# FLY_DIVER.net
KiCad netlist of a schematic drawn in Altium Designer
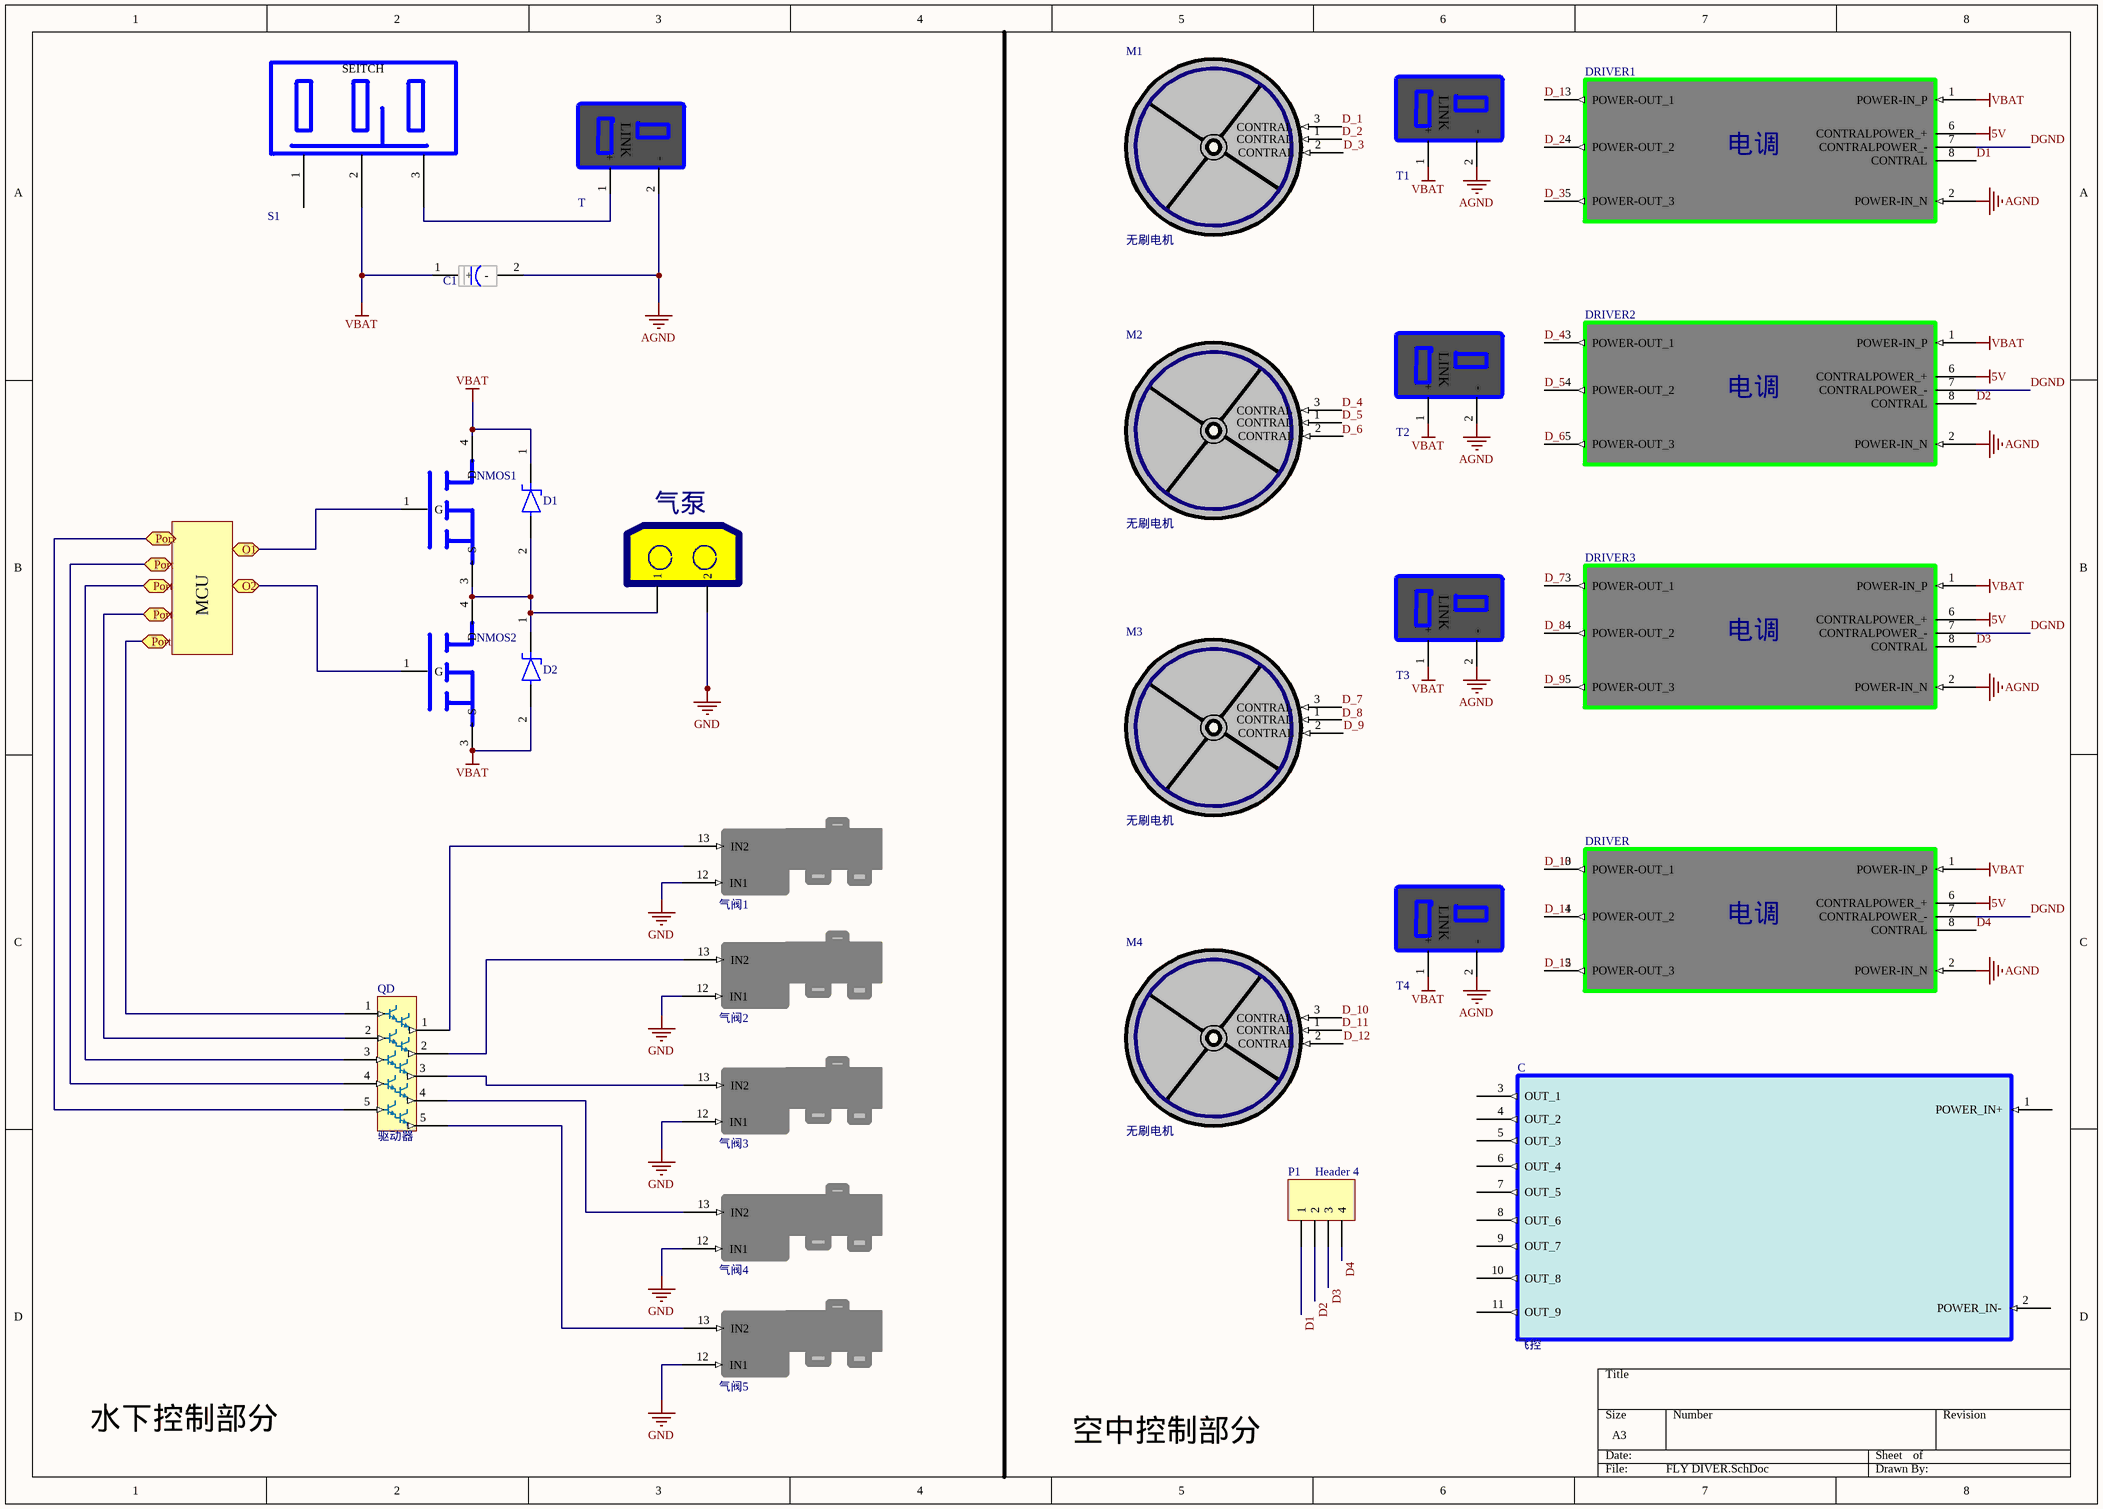
[diagram p0: FLY DIVER.SchDoc]

(export (version "E")
  (design (tool "Eeschema 10.0.6"))
  (components
    (comp (ref "*") (value "MCU") (libsource (lib "FLY DIVER") (part "MCU")))
    (comp (ref "C") (value "飞控") (libsource (lib "FLY DIVER") (part "飞控")))
    (comp (ref "C1") (value "钽电容") (footprint "钽B") (libsource (lib "常用原件库") (part "钽电容")))
    (comp (ref "D1") (value "贴片二极管") (footprint "二极管SMA") (libsource (lib "常用原件库") (part "贴片二极管")))
    (comp (ref "D2") (value "贴片二极管") (footprint "二极管SMA") (libsource (lib "常用原件库") (part "贴片二极管")))
    (comp (ref "DRIVER") (value "U?") (libsource (lib "FLY DIVER") (part "电调")))
    (comp (ref "DRIVER1") (value "U?") (libsource (lib "FLY DIVER") (part "电调")))
    (comp (ref "DRIVER2") (value "U?") (libsource (lib "FLY DIVER") (part "电调")))
    (comp (ref "DRIVER3") (value "U?") (libsource (lib "FLY DIVER") (part "电调")))
    (comp (ref "M1") (value "无刷电机") (libsource (lib "FLY DIVER") (part "无刷电机")))
    (comp (ref "M2") (value "无刷电机") (libsource (lib "FLY DIVER") (part "无刷电机")))
    (comp (ref "M3") (value "无刷电机") (libsource (lib "FLY DIVER") (part "无刷电机")))
    (comp (ref "M4") (value "无刷电机") (libsource (lib "FLY DIVER") (part "无刷电机")))
    (comp (ref "NMOS1") (value "NMOS") (footprint "NMOS") (libsource (lib "常用原件库") (part "NMOS")))
    (comp (ref "NMOS2") (value "NMOS") (footprint "NMOS") (libsource (lib "常用原件库") (part "NMOS")))
    (comp (ref "P1")
      (value "Header 4")
      (footprint "HDR1X4")
      (description "Header, 4-Pin")
      (fields (field (name "PUBLISHER") "Altium Limited"))
      (libsource (lib "Miscellaneous Connectors") (part "Header 4"))
    )
    (comp (ref "Q1") (value "气阀1") (libsource (lib "FLY DIVER") (part "气阀")))
    (comp (ref "Q2") (value "气阀2") (libsource (lib "FLY DIVER") (part "气阀")))
    (comp (ref "Q3") (value "气阀3") (libsource (lib "FLY DIVER") (part "气阀")))
    (comp (ref "Q4") (value "气阀4") (libsource (lib "FLY DIVER") (part "气阀")))
    (comp (ref "Q5") (value "气阀5") (libsource (lib "FLY DIVER") (part "气阀")))
    (comp (ref "QD") (value "驱动器") (libsource (lib "FLY DIVER") (part "驱动器")))
    (comp (ref "S1") (value "拨动开关") (footprint "拨动开关") (libsource (lib "常用原件库") (part "拨动开关")))
    (comp (ref "T") (value "T型头") (footprint "T型头") (libsource (lib "常用原件库") (part "T型头")))
    (comp (ref "T1") (value "T型头") (footprint "T型头") (libsource (lib "常用原件库") (part "T型头")))
    (comp (ref "T2") (value "T型头") (footprint "T型头") (libsource (lib "常用原件库") (part "T型头")))
    (comp (ref "T3") (value "T型头") (footprint "T型头") (libsource (lib "常用原件库") (part "T型头")))
    (comp (ref "T4") (value "T型头") (footprint "T型头") (libsource (lib "常用原件库") (part "T型头")))
    (comp (ref "气泵") (value "P") (footprint "2脚接头") (libsource (lib "常用原件库") (part "2脚接头")))
  )
  (nets
    (net (code "1") (name "/D1") (class "Default")
      (node (ref "DRIVER1") (pin "8") (pinfunction "CONTRAL_8") (pintype "passive"))
      (node (ref "P1") (pin "1") (pinfunction "1_1") (pintype "passive"))
    )
    (net (code "2") (name "/D2") (class "Default")
      (node (ref "DRIVER2") (pin "8") (pinfunction "CONTRAL_8") (pintype "passive"))
      (node (ref "P1") (pin "2") (pinfunction "2_2") (pintype "passive"))
    )
    (net (code "3") (name "/D3") (class "Default")
      (node (ref "DRIVER3") (pin "8") (pinfunction "CONTRAL_8") (pintype "passive"))
      (node (ref "P1") (pin "3") (pinfunction "3_3") (pintype "passive"))
    )
    (net (code "4") (name "/D4") (class "Default")
      (node (ref "DRIVER") (pin "8") (pinfunction "CONTRAL_8") (pintype "passive"))
      (node (ref "P1") (pin "4") (pinfunction "4_4") (pintype "passive"))
    )
    (net (code "5") (name "/DGND") (class "Default")
      (node (ref "DRIVER") (pin "7") (pinfunction "CONTRALPOWER_-_7") (pintype "passive"))
      (node (ref "DRIVER1") (pin "7") (pinfunction "CONTRALPOWER_-_7") (pintype "passive"))
      (node (ref "DRIVER2") (pin "7") (pinfunction "CONTRALPOWER_-_7") (pintype "passive"))
      (node (ref "DRIVER3") (pin "7") (pinfunction "CONTRALPOWER_-_7") (pintype "passive"))
    )
    (net (code "6") (name "/D_1") (class "Default")
      (node (ref "DRIVER1") (pin "3") (pinfunction "POWER-OUT_1_3") (pintype "output"))
      (node (ref "M1") (pin "3") (pinfunction "CONTRAL_3") (pintype "input"))
    )
    (net (code "7") (name "/D_2") (class "Default")
      (node (ref "DRIVER1") (pin "4") (pinfunction "POWER-OUT_2_4") (pintype "output"))
      (node (ref "M1") (pin "1") (pinfunction "CONTRAL_1") (pintype "input"))
    )
    (net (code "8") (name "/D_3") (class "Default")
      (node (ref "DRIVER1") (pin "5") (pinfunction "POWER-OUT_3_5") (pintype "output"))
      (node (ref "M1") (pin "2") (pinfunction "CONTRAL_2") (pintype "input"))
    )
    (net (code "9") (name "/D_4") (class "Default")
      (node (ref "DRIVER2") (pin "3") (pinfunction "POWER-OUT_1_3") (pintype "output"))
      (node (ref "M2") (pin "3") (pinfunction "CONTRAL_3") (pintype "input"))
    )
    (net (code "10") (name "/D_5") (class "Default")
      (node (ref "DRIVER2") (pin "4") (pinfunction "POWER-OUT_2_4") (pintype "output"))
      (node (ref "M2") (pin "1") (pinfunction "CONTRAL_1") (pintype "input"))
    )
    (net (code "11") (name "/D_6") (class "Default")
      (node (ref "DRIVER2") (pin "5") (pinfunction "POWER-OUT_3_5") (pintype "output"))
    )
    (net (code "12") (name "/D_7") (class "Default")
      (node (ref "DRIVER3") (pin "3") (pinfunction "POWER-OUT_1_3") (pintype "output"))
      (node (ref "M3") (pin "3") (pinfunction "CONTRAL_3") (pintype "input"))
    )
    (net (code "13") (name "/D_8") (class "Default")
      (node (ref "DRIVER3") (pin "4") (pinfunction "POWER-OUT_2_4") (pintype "output"))
    )
    (net (code "14") (name "/D_9") (class "Default")
      (node (ref "DRIVER3") (pin "5") (pinfunction "POWER-OUT_3_5") (pintype "output"))
      (node (ref "M3") (pin "2") (pinfunction "CONTRAL_2") (pintype "input"))
    )
    (net (code "15") (name "/D_10") (class "Default")
      (node (ref "DRIVER") (pin "3") (pinfunction "POWER-OUT_1_3") (pintype "output"))
      (node (ref "M4") (pin "3") (pinfunction "CONTRAL_3") (pintype "input"))
    )
    (net (code "16") (name "/D_11") (class "Default")
      (node (ref "DRIVER") (pin "4") (pinfunction "POWER-OUT_2_4") (pintype "output"))
      (node (ref "M4") (pin "1") (pinfunction "CONTRAL_1") (pintype "input"))
    )
    (net (code "17") (name "/D_12") (class "Default")
      (node (ref "DRIVER") (pin "5") (pinfunction "POWER-OUT_3_5") (pintype "output"))
      (node (ref "M4") (pin "2") (pinfunction "CONTRAL_2") (pintype "input"))
    )
    (net (code "18") (name "/O1") (class "Default")
      (node (ref "NMOS1") (pin "1") (pinfunction "G_1") (pintype "passive"))
    )
    (net (code "19") (name "/O2") (class "Default")
      (node (ref "NMOS2") (pin "1") (pinfunction "G_1") (pintype "passive"))
    )
    (net (code "20") (name "/Port") (class "Default")
      (node (ref "QD") (pin "1") (pinfunction "IN_1") (pintype "input"))
      (node (ref "QD") (pin "2") (pinfunction "IN_2") (pintype "input"))
      (node (ref "QD") (pin "3") (pinfunction "IN_3") (pintype "input"))
      (node (ref "QD") (pin "4") (pinfunction "IN_4") (pintype "input"))
      (node (ref "QD") (pin "5") (pinfunction "IN_5") (pintype "input"))
    )
    (net (code "21") (name "5V") (class "Default")
      (node (ref "DRIVER") (pin "6") (pinfunction "CONTRALPOWER_+_6") (pintype "passive"))
      (node (ref "DRIVER1") (pin "6") (pinfunction "CONTRALPOWER_+_6") (pintype "passive"))
      (node (ref "DRIVER2") (pin "6") (pinfunction "CONTRALPOWER_+_6") (pintype "passive"))
      (node (ref "DRIVER3") (pin "6") (pinfunction "CONTRALPOWER_+_6") (pintype "passive"))
    )
    (net (code "22") (name "AGND") (class "Default")
      (node (ref "C1") (pin "2") (pinfunction "-_2") (pintype "passive"))
      (node (ref "DRIVER") (pin "2") (pinfunction "POWER-IN_N_2") (pintype "input"))
      (node (ref "DRIVER1") (pin "2") (pinfunction "POWER-IN_N_2") (pintype "input"))
      (node (ref "DRIVER2") (pin "2") (pinfunction "POWER-IN_N_2") (pintype "input"))
      (node (ref "DRIVER3") (pin "2") (pinfunction "POWER-IN_N_2") (pintype "input"))
      (node (ref "T") (pin "2") (pinfunction "-_2") (pintype "passive"))
      (node (ref "T1") (pin "2") (pinfunction "-_2") (pintype "passive"))
      (node (ref "T2") (pin "2") (pinfunction "-_2") (pintype "passive"))
      (node (ref "T3") (pin "2") (pinfunction "-_2") (pintype "passive"))
      (node (ref "T4") (pin "2") (pinfunction "-_2") (pintype "passive"))
    )
    (net (code "23") (name "GND") (class "Default")
      (node (ref "Q1") (pin "12") (pinfunction "IN1_12") (pintype "input"))
      (node (ref "Q2") (pin "12") (pinfunction "IN1_12") (pintype "input"))
      (node (ref "Q3") (pin "12") (pinfunction "IN1_12") (pintype "input"))
      (node (ref "Q4") (pin "12") (pinfunction "IN1_12") (pintype "input"))
      (node (ref "Q5") (pin "12") (pinfunction "IN1_12") (pintype "input"))
      (node (ref "气泵") (pin "2") (pinfunction "2_2") (pintype "passive"))
    )
    (net (code "24") (name "Net-(NMOS1-S)") (class "Default")
      (node (ref "D1") (pin "2") (pinfunction "2_2") (pintype "passive"))
      (node (ref "D2") (pin "1") (pinfunction "1_1") (pintype "passive"))
      (node (ref "NMOS1") (pin "3") (pinfunction "S_3") (pintype "passive"))
      (node (ref "NMOS2") (pin "4") (pinfunction "D_4") (pintype "passive"))
      (node (ref "气泵") (pin "1") (pinfunction "1_1") (pintype "passive"))
    )
    (net (code "25") (name "Net-(Q1-IN2)") (class "Default")
      (node (ref "Q1") (pin "13") (pinfunction "IN2_13") (pintype "input"))
      (node (ref "QD") (pin "1") (pinfunction "OUT_1") (pintype "output"))
    )
    (net (code "26") (name "Net-(Q2-IN2)") (class "Default")
      (node (ref "Q2") (pin "13") (pinfunction "IN2_13") (pintype "input"))
      (node (ref "QD") (pin "2") (pinfunction "OUT_2") (pintype "output"))
    )
    (net (code "27") (name "Net-(Q3-IN2)") (class "Default")
      (node (ref "Q3") (pin "13") (pinfunction "IN2_13") (pintype "input"))
      (node (ref "QD") (pin "3") (pinfunction "OUT_3") (pintype "output"))
    )
    (net (code "28") (name "Net-(Q4-IN2)") (class "Default")
      (node (ref "Q4") (pin "13") (pinfunction "IN2_13") (pintype "input"))
      (node (ref "QD") (pin "4") (pinfunction "OUT_4") (pintype "output"))
    )
    (net (code "29") (name "Net-(Q5-IN2)") (class "Default")
      (node (ref "Q5") (pin "13") (pinfunction "IN2_13") (pintype "input"))
      (node (ref "QD") (pin "5") (pinfunction "OUT_5") (pintype "output"))
    )
    (net (code "30") (name "Net-(T-+)") (class "Default")
      (node (ref "S1") (pin "3") (pinfunction "3_3") (pintype "passive"))
      (node (ref "T") (pin "1") (pinfunction "+_1") (pintype "passive"))
    )
    (net (code "31") (name "VBAT") (class "Default")
      (node (ref "C1") (pin "1") (pinfunction "+_1") (pintype "passive"))
      (node (ref "D1") (pin "1") (pinfunction "1_1") (pintype "passive"))
      (node (ref "D2") (pin "2") (pinfunction "2_2") (pintype "passive"))
      (node (ref "DRIVER") (pin "1") (pinfunction "POWER-IN_P_1") (pintype "input"))
      (node (ref "DRIVER1") (pin "1") (pinfunction "POWER-IN_P_1") (pintype "input"))
      (node (ref "DRIVER2") (pin "1") (pinfunction "POWER-IN_P_1") (pintype "input"))
      (node (ref "DRIVER3") (pin "1") (pinfunction "POWER-IN_P_1") (pintype "input"))
      (node (ref "NMOS1") (pin "4") (pinfunction "D_4") (pintype "passive"))
      (node (ref "NMOS2") (pin "3") (pinfunction "S_3") (pintype "passive"))
      (node (ref "S1") (pin "2") (pinfunction "2_2") (pintype "passive"))
      (node (ref "T1") (pin "1") (pinfunction "+_1") (pintype "passive"))
      (node (ref "T2") (pin "1") (pinfunction "+_1") (pintype "passive"))
      (node (ref "T3") (pin "1") (pinfunction "+_1") (pintype "passive"))
      (node (ref "T4") (pin "1") (pinfunction "+_1") (pintype "passive"))
    )
    (net (code "32") (name "unconnected-(C-OUT_1-Pad3)") (class "Default")
      (node (ref "C") (pin "3") (pinfunction "OUT_1_3") (pintype "output"))
    )
    (net (code "33") (name "unconnected-(C-OUT_2-Pad4)") (class "Default")
      (node (ref "C") (pin "4") (pinfunction "OUT_2_4") (pintype "output"))
    )
    (net (code "34") (name "unconnected-(C-OUT_3-Pad5)") (class "Default")
      (node (ref "C") (pin "5") (pinfunction "OUT_3_5") (pintype "output"))
    )
    (net (code "35") (name "unconnected-(C-OUT_4-Pad6)") (class "Default")
      (node (ref "C") (pin "6") (pinfunction "OUT_4_6") (pintype "output"))
    )
    (net (code "36") (name "unconnected-(C-OUT_5-Pad7)") (class "Default")
      (node (ref "C") (pin "7") (pinfunction "OUT_5_7") (pintype "output"))
    )
    (net (code "37") (name "unconnected-(C-OUT_6-Pad8)") (class "Default")
      (node (ref "C") (pin "8") (pinfunction "OUT_6_8") (pintype "output"))
    )
    (net (code "38") (name "unconnected-(C-OUT_7-Pad9)") (class "Default")
      (node (ref "C") (pin "9") (pinfunction "OUT_7_9") (pintype "output"))
    )
    (net (code "39") (name "unconnected-(C-OUT_8-Pad10)") (class "Default")
      (node (ref "C") (pin "10") (pinfunction "OUT_8_10") (pintype "output"))
    )
    (net (code "40") (name "unconnected-(C-OUT_9-Pad11)") (class "Default")
      (node (ref "C") (pin "11") (pinfunction "OUT_9_11") (pintype "output"))
    )
    (net (code "41") (name "unconnected-(C-POWER_IN+-Pad1)") (class "Default")
      (node (ref "C") (pin "1") (pinfunction "POWER_IN+_1") (pintype "input"))
    )
    (net (code "42") (name "unconnected-(C-POWER_IN--Pad2)") (class "Default")
      (node (ref "C") (pin "2") (pinfunction "POWER_IN-_2") (pintype "input"))
    )
    (net (code "43") (name "unconnected-(M2-CONTRAL-Pad2)") (class "Default")
      (node (ref "M2") (pin "2") (pinfunction "CONTRAL_2") (pintype "input"))
    )
    (net (code "44") (name "unconnected-(M3-CONTRAL-Pad1)") (class "Default")
      (node (ref "M3") (pin "1") (pinfunction "CONTRAL_1") (pintype "input"))
    )
    (net (code "45") (name "unconnected-(S1-Pad1)") (class "Default")
      (node (ref "S1") (pin "1") (pinfunction "1_1") (pintype "passive"))
    )
  )
)
